# 640mk4.net
KiCad netlist of a schematic drawn in EAGLE
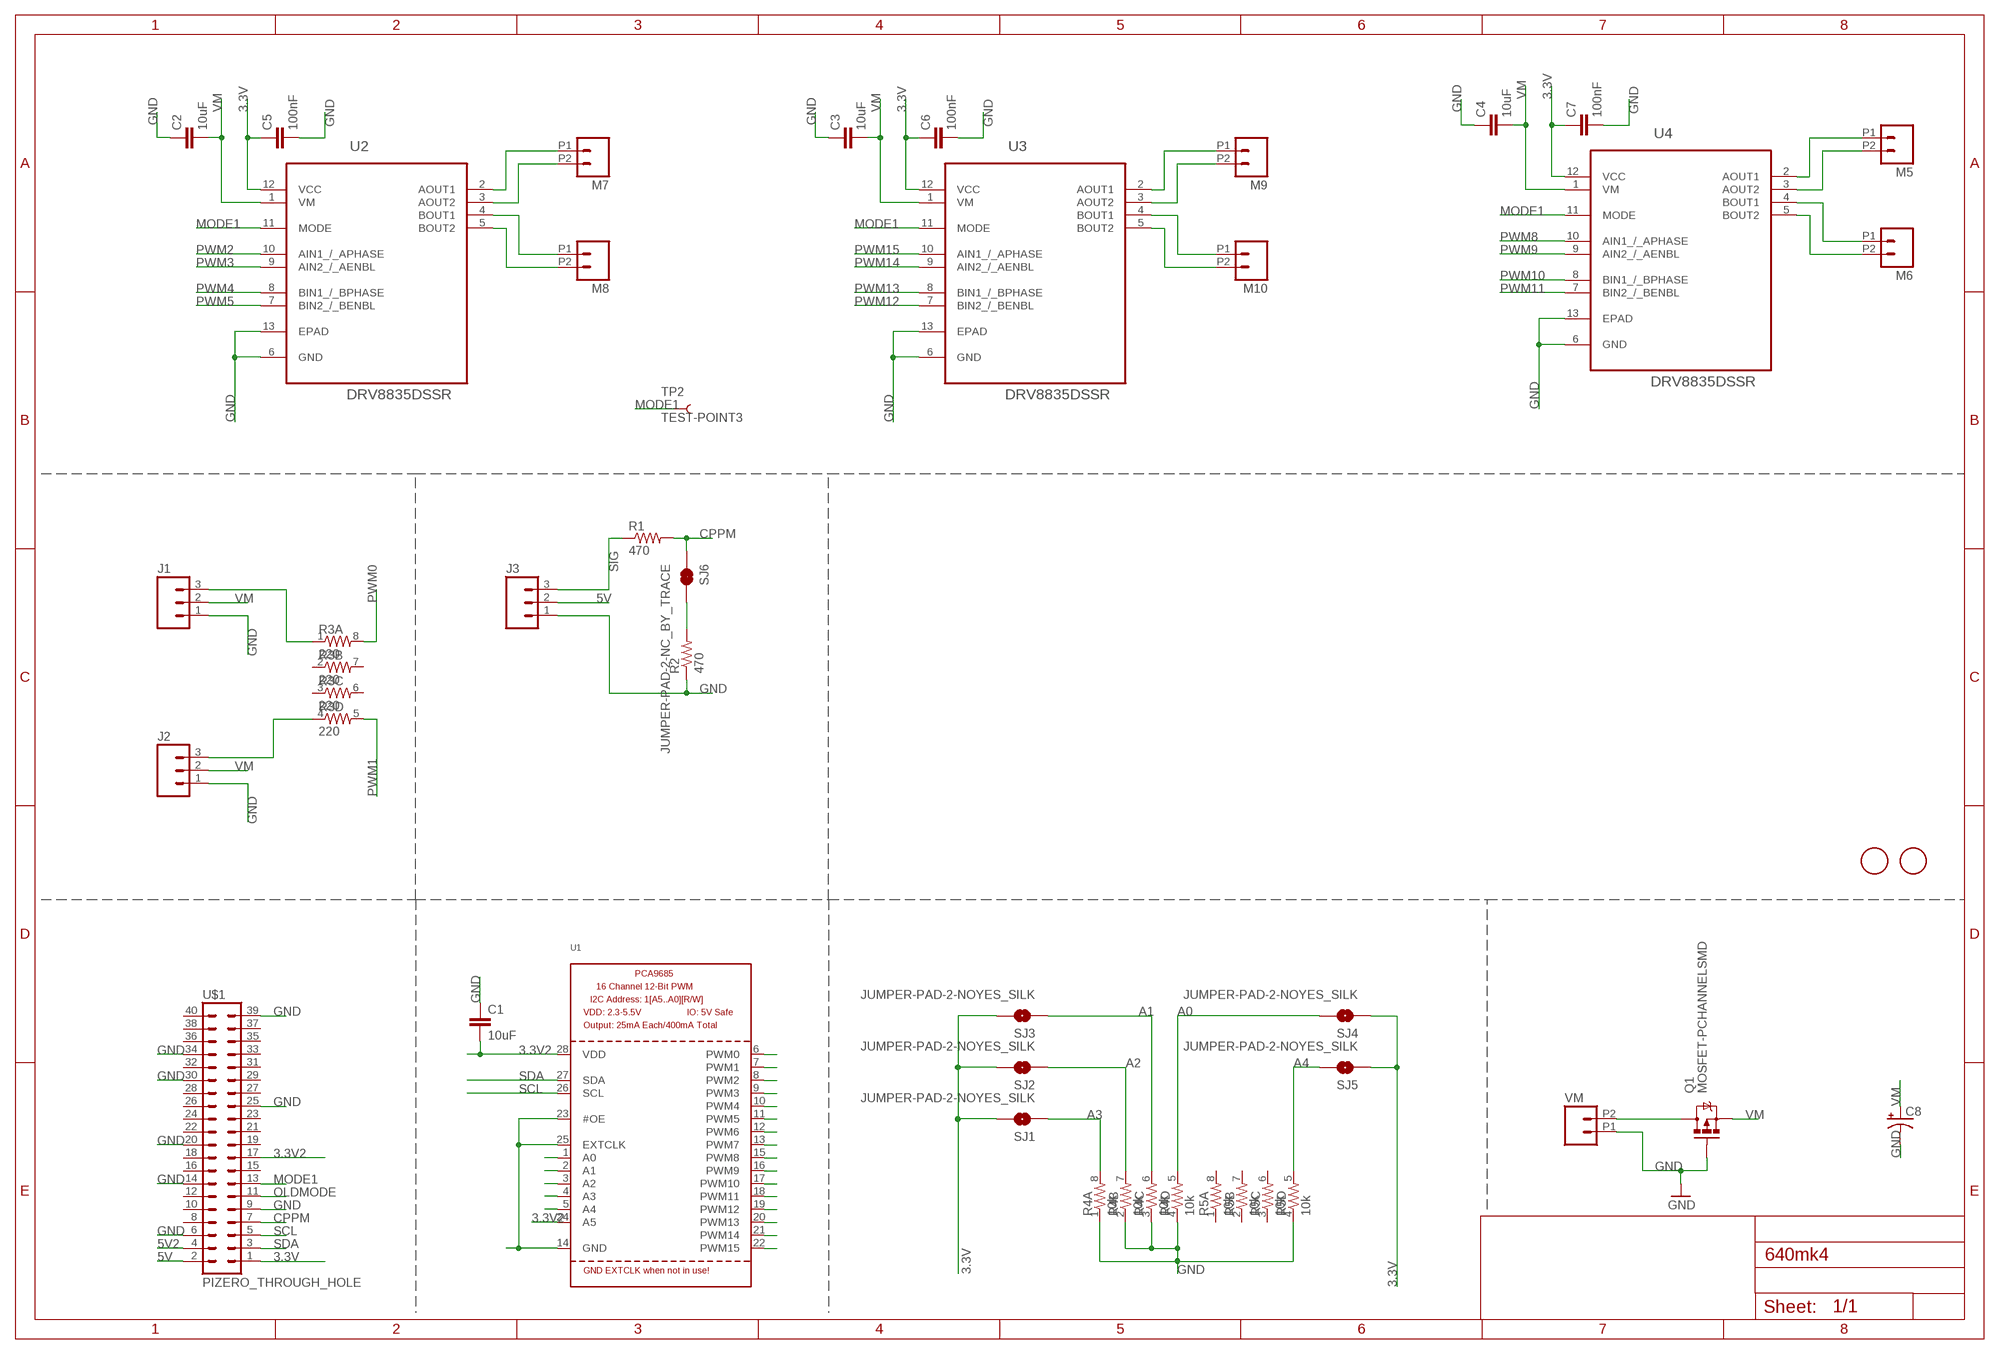
[diagram p0: schematic, sheet 1]

(export (version "E")
  (design (tool "Eeschema 10.0.6"))
  (components
    (comp (ref "C1")
      (value "10uF")
      (footprint "eagle-import:0805")
      (libsource (lib "eagle-import") (part "CAP0805"))
    )
    (comp (ref "C2")
      (value "10uF")
      (footprint "eagle-import:0805")
      (libsource (lib "eagle-import") (part "CAP0805"))
    )
    (comp (ref "C3")
      (value "10uF")
      (footprint "eagle-import:0805")
      (libsource (lib "eagle-import") (part "CAP0805"))
    )
    (comp (ref "C4")
      (value "10uF")
      (footprint "eagle-import:0805")
      (libsource (lib "eagle-import") (part "CAP0805"))
    )
    (comp (ref "C5")
      (value "100nF")
      (footprint "eagle-import:0805")
      (libsource (lib "eagle-import") (part "CAP0805"))
    )
    (comp (ref "C6")
      (value "100nF")
      (footprint "eagle-import:0805")
      (libsource (lib "eagle-import") (part "CAP0805"))
    )
    (comp (ref "C7")
      (value "100nF")
      (footprint "eagle-import:0805")
      (libsource (lib "eagle-import") (part "CAP0805"))
    )
    (comp (ref "C8")
      (value "CAP_POLPTH1")
      (footprint "eagle-import:CPOL-RADIAL-100UF-25V")
      (libsource (lib "eagle-import") (part "CAP_POLPTH1"))
    )
    (comp (ref "FID1")
      (value "FIDUCIAL")
      (footprint "eagle-import:FIDUCIAL_1MM")
      (libsource (lib "eagle-import") (part "FIDUCIAL"))
    )
    (comp (ref "FID2")
      (value "FIDUCIAL")
      (footprint "eagle-import:FIDUCIAL_1MM")
      (libsource (lib "eagle-import") (part "FIDUCIAL"))
    )
    (comp (ref "J1")
      (value "M03LOCK")
      (footprint "eagle-import:1X03_LOCK")
      (libsource (lib "eagle-import") (part "M03LOCK"))
    )
    (comp (ref "J2")
      (value "M03LOCK")
      (footprint "eagle-import:1X03_LOCK")
      (libsource (lib "eagle-import") (part "M03LOCK"))
    )
    (comp (ref "J3")
      (value "M03LOCK")
      (footprint "eagle-import:1X03_LOCK")
      (libsource (lib "eagle-import") (part "M03LOCK"))
    )
    (comp (ref "M5")
      (value "M022.54MM_SCREWTERM")
      (footprint "eagle-import:1X02_2.54_SCREWTERM")
      (libsource (lib "eagle-import") (part "M022.54MM_SCREWTERM"))
    )
    (comp (ref "M6")
      (value "M022.54MM_SCREWTERM")
      (footprint "eagle-import:1X02_2.54_SCREWTERM")
      (libsource (lib "eagle-import") (part "M022.54MM_SCREWTERM"))
    )
    (comp (ref "M7")
      (value "M022.54MM_SCREWTERM")
      (footprint "eagle-import:1X02_2.54_SCREWTERM")
      (libsource (lib "eagle-import") (part "M022.54MM_SCREWTERM"))
    )
    (comp (ref "M8")
      (value "M022.54MM_SCREWTERM")
      (footprint "eagle-import:1X02_2.54_SCREWTERM")
      (libsource (lib "eagle-import") (part "M022.54MM_SCREWTERM"))
    )
    (comp (ref "M9")
      (value "M022.54MM_SCREWTERM")
      (footprint "eagle-import:1X02_2.54_SCREWTERM")
      (libsource (lib "eagle-import") (part "M022.54MM_SCREWTERM"))
    )
    (comp (ref "M10")
      (value "M022.54MM_SCREWTERM")
      (footprint "eagle-import:1X02_2.54_SCREWTERM")
      (libsource (lib "eagle-import") (part "M022.54MM_SCREWTERM"))
    )
    (comp (ref "Q1")
      (value "MOSFET-PCHANNELSMD")
      (footprint "eagle-import:SOT23-3")
      (libsource (lib "eagle-import") (part "MOSFET-PCHANNELSMD"))
    )
    (comp (ref "R1")
      (value "470")
      (footprint "eagle-import:0805")
      (libsource (lib "eagle-import") (part "RESISTOR0805-RES"))
    )
    (comp (ref "R2")
      (value "470")
      (footprint "eagle-import:0805")
      (libsource (lib "eagle-import") (part "RESISTOR0805-RES"))
    )
    (comp (ref "R3")
      (value "220")
      (footprint "eagle-import:0603-ARV")
      (libsource (lib "eagle-import") (part "RESISTOR-ARRAY0603-ARV"))
    )
    (comp (ref "R4")
      (value "10k")
      (footprint "eagle-import:0603-ARV")
      (libsource (lib "eagle-import") (part "RESISTOR-ARRAY0603-ARV"))
    )
    (comp (ref "R5")
      (value "10k")
      (footprint "eagle-import:0603-ARV")
      (libsource (lib "eagle-import") (part "RESISTOR-ARRAY0603-ARV"))
    )
    (comp (ref "SJ1")
      (value "JUMPER-PAD-2-NOYES_SILK")
      (footprint "eagle-import:PAD-JUMPER-2-NO_YES_SILK")
      (libsource (lib "eagle-import") (part "JUMPER-PAD-2-NOYES_SILK"))
    )
    (comp (ref "SJ2")
      (value "JUMPER-PAD-2-NOYES_SILK")
      (footprint "eagle-import:PAD-JUMPER-2-NO_YES_SILK")
      (libsource (lib "eagle-import") (part "JUMPER-PAD-2-NOYES_SILK"))
    )
    (comp (ref "SJ3")
      (value "JUMPER-PAD-2-NOYES_SILK")
      (footprint "eagle-import:PAD-JUMPER-2-NO_YES_SILK")
      (libsource (lib "eagle-import") (part "JUMPER-PAD-2-NOYES_SILK"))
    )
    (comp (ref "SJ4")
      (value "JUMPER-PAD-2-NOYES_SILK")
      (footprint "eagle-import:PAD-JUMPER-2-NO_YES_SILK")
      (libsource (lib "eagle-import") (part "JUMPER-PAD-2-NOYES_SILK"))
    )
    (comp (ref "SJ5")
      (value "JUMPER-PAD-2-NOYES_SILK")
      (footprint "eagle-import:PAD-JUMPER-2-NO_YES_SILK")
      (libsource (lib "eagle-import") (part "JUMPER-PAD-2-NOYES_SILK"))
    )
    (comp (ref "SJ6")
      (value "JUMPER-PAD-2-NC_BY_TRACE")
      (footprint "eagle-import:PAD-JUMPER-2-NC_BY_TRACE_YES_SILK")
      (libsource (lib "eagle-import") (part "JUMPER-PAD-2-NC_BY_TRACE"))
    )
    (comp (ref "TP2")
      (value "TEST-POINT3")
      (footprint "eagle-import:PAD.03X.03")
      (libsource (lib "eagle-import") (part "TEST-POINT3"))
    )
    (comp (ref "U$1")
      (value "PIZERO_THROUGH_HOLE")
      (footprint "eagle-import:PIZERO_THOUGH_HOLE")
      (libsource (lib "eagle-import") (part "PIZERO_THROUGH_HOLE"))
    )
    (comp (ref "U1")
      (value "PCA9685")
      (footprint "eagle-import:TSSOP28")
      (libsource (lib "eagle-import") (part "PCA9685"))
    )
    (comp (ref "U2")
      (value "DRV8835DSSR")
      (footprint "eagle-import:SON50P200X300X80-13N")
      (fields (field (name "MPN") "DRV8835DSSR "))
      (libsource (lib "eagle-import") (part "DRV8835DSSR"))
    )
    (comp (ref "U3")
      (value "DRV8835DSSR")
      (footprint "eagle-import:SON50P200X300X80-13N")
      (fields (field (name "MPN") "DRV8835DSSR "))
      (libsource (lib "eagle-import") (part "DRV8835DSSR"))
    )
    (comp (ref "U4")
      (value "DRV8835DSSR")
      (footprint "eagle-import:SON50P200X300X80-13N")
      (fields (field (name "MPN") "DRV8835DSSR "))
      (libsource (lib "eagle-import") (part "DRV8835DSSR"))
    )
    (comp (ref "VM")
      (value "M022.54MM_SCREWTERM")
      (footprint "eagle-import:1X02_2.54_SCREWTERM")
      (libsource (lib "eagle-import") (part "M022.54MM_SCREWTERM"))
    )
  )
  (nets
    (net (code "1") (name "/3.3V") (class "Default")
      (node (ref "C5") (pin "1") (pinfunction "1_1") (pintype "passive"))
      (node (ref "C6") (pin "1") (pinfunction "1_1") (pintype "passive"))
      (node (ref "C7") (pin "1") (pinfunction "1_1") (pintype "passive"))
      (node (ref "SJ1") (pin "2") (pinfunction "2_2") (pintype "passive"))
      (node (ref "SJ2") (pin "2") (pinfunction "2_2") (pintype "passive"))
      (node (ref "SJ3") (pin "2") (pinfunction "2_2") (pintype "passive"))
      (node (ref "SJ4") (pin "1") (pinfunction "1_1") (pintype "passive"))
      (node (ref "SJ5") (pin "1") (pinfunction "1_1") (pintype "passive"))
      (node (ref "U$1") (pin "1") (pinfunction "1_1") (pintype "passive"))
      (node (ref "U2") (pin "12") (pinfunction "VCC_12") (pintype "power_in"))
      (node (ref "U3") (pin "12") (pinfunction "VCC_12") (pintype "power_in"))
      (node (ref "U4") (pin "12") (pinfunction "VCC_12") (pintype "power_in"))
    )
    (net (code "2") (name "/3.3V2") (class "Default")
      (node (ref "C1") (pin "2") (pinfunction "2_2") (pintype "passive"))
      (node (ref "U$1") (pin "17") (pinfunction "17_17") (pintype "passive"))
      (node (ref "U1") (pin "24") (pinfunction "A5_24") (pintype "bidirectional"))
      (node (ref "U1") (pin "28") (pinfunction "VDD_28") (pintype "power_in"))
    )
    (net (code "3") (name "/5V") (class "Default")
      (node (ref "J3") (pin "2") (pinfunction "2_2") (pintype "passive"))
      (node (ref "U$1") (pin "2") (pinfunction "2_2") (pintype "passive"))
    )
    (net (code "4") (name "/5V2") (class "Default")
      (node (ref "U$1") (pin "4") (pinfunction "4_4") (pintype "passive"))
    )
    (net (code "5") (name "/A0") (class "Default")
      (node (ref "R4") (pin "5") (pinfunction "2_5") (pintype "passive"))
      (node (ref "SJ4") (pin "2") (pinfunction "2_2") (pintype "passive"))
      (node (ref "U1") (pin "1") (pinfunction "A0_1") (pintype "bidirectional"))
    )
    (net (code "6") (name "/A1") (class "Default")
      (node (ref "R4") (pin "6") (pinfunction "2_6") (pintype "passive"))
      (node (ref "SJ3") (pin "1") (pinfunction "1_1") (pintype "passive"))
      (node (ref "U1") (pin "2") (pinfunction "A1_2") (pintype "bidirectional"))
    )
    (net (code "7") (name "/A2") (class "Default")
      (node (ref "R4") (pin "7") (pinfunction "2_7") (pintype "passive"))
      (node (ref "SJ2") (pin "1") (pinfunction "1_1") (pintype "passive"))
      (node (ref "U1") (pin "3") (pinfunction "A2_3") (pintype "bidirectional"))
    )
    (net (code "8") (name "/A3") (class "Default")
      (node (ref "R4") (pin "8") (pinfunction "2_8") (pintype "passive"))
      (node (ref "SJ1") (pin "1") (pinfunction "1_1") (pintype "passive"))
      (node (ref "U1") (pin "4") (pinfunction "A3_4") (pintype "bidirectional"))
    )
    (net (code "9") (name "/A4") (class "Default")
      (node (ref "R5") (pin "5") (pinfunction "2_5") (pintype "passive"))
      (node (ref "SJ5") (pin "2") (pinfunction "2_2") (pintype "passive"))
      (node (ref "U1") (pin "5") (pinfunction "A4_5") (pintype "bidirectional"))
    )
    (net (code "10") (name "/CPPM") (class "Default")
      (node (ref "R1") (pin "2") (pinfunction "2_2") (pintype "passive"))
      (node (ref "SJ6") (pin "1") (pinfunction "1_1") (pintype "passive"))
      (node (ref "U$1") (pin "7") (pinfunction "7_7") (pintype "passive"))
    )
    (net (code "11") (name "/MODE1") (class "Default")
      (node (ref "TP2") (pin "P$1") (pinfunction "1_P$1") (pintype "bidirectional"))
      (node (ref "U$1") (pin "13") (pinfunction "13_13") (pintype "passive"))
      (node (ref "U2") (pin "11") (pinfunction "MODE_11") (pintype "input"))
      (node (ref "U3") (pin "11") (pinfunction "MODE_11") (pintype "input"))
      (node (ref "U4") (pin "11") (pinfunction "MODE_11") (pintype "input"))
    )
    (net (code "12") (name "/OLDMODE") (class "Default")
      (node (ref "U$1") (pin "11") (pinfunction "11_11") (pintype "passive"))
    )
    (net (code "13") (name "/PWM0") (class "Default")
      (node (ref "R3") (pin "8") (pinfunction "2_8") (pintype "passive"))
      (node (ref "U1") (pin "6") (pinfunction "PWM0_6") (pintype "output"))
    )
    (net (code "14") (name "/PWM1") (class "Default")
      (node (ref "R3") (pin "5") (pinfunction "2_5") (pintype "passive"))
      (node (ref "U1") (pin "7") (pinfunction "PWM1_7") (pintype "output"))
    )
    (net (code "15") (name "/PWM2") (class "Default")
      (node (ref "U1") (pin "8") (pinfunction "PWM2_8") (pintype "output"))
      (node (ref "U2") (pin "10") (pinfunction "AIN1_/_APHASE_10") (pintype "input"))
    )
    (net (code "16") (name "/PWM3") (class "Default")
      (node (ref "U1") (pin "9") (pinfunction "PWM3_9") (pintype "output"))
      (node (ref "U2") (pin "9") (pinfunction "AIN2_/_AENBL_9") (pintype "input"))
    )
    (net (code "17") (name "/PWM4") (class "Default")
      (node (ref "U1") (pin "10") (pinfunction "PWM4_10") (pintype "output"))
      (node (ref "U2") (pin "8") (pinfunction "BIN1_/_BPHASE_8") (pintype "input"))
    )
    (net (code "18") (name "/PWM5") (class "Default")
      (node (ref "U1") (pin "11") (pinfunction "PWM5_11") (pintype "output"))
      (node (ref "U2") (pin "7") (pinfunction "BIN2_/_BENBL_7") (pintype "input"))
    )
    (net (code "19") (name "/PWM8") (class "Default")
      (node (ref "U1") (pin "15") (pinfunction "PWM8_15") (pintype "output"))
      (node (ref "U4") (pin "10") (pinfunction "AIN1_/_APHASE_10") (pintype "input"))
    )
    (net (code "20") (name "/PWM9") (class "Default")
      (node (ref "U1") (pin "16") (pinfunction "PWM9_16") (pintype "output"))
      (node (ref "U4") (pin "9") (pinfunction "AIN2_/_AENBL_9") (pintype "input"))
    )
    (net (code "21") (name "/PWM10") (class "Default")
      (node (ref "U1") (pin "17") (pinfunction "PWM10_17") (pintype "output"))
      (node (ref "U4") (pin "8") (pinfunction "BIN1_/_BPHASE_8") (pintype "input"))
    )
    (net (code "22") (name "/PWM11") (class "Default")
      (node (ref "U1") (pin "18") (pinfunction "PWM11_18") (pintype "output"))
      (node (ref "U4") (pin "7") (pinfunction "BIN2_/_BENBL_7") (pintype "input"))
    )
    (net (code "23") (name "/PWM12") (class "Default")
      (node (ref "U1") (pin "19") (pinfunction "PWM12_19") (pintype "output"))
      (node (ref "U3") (pin "7") (pinfunction "BIN2_/_BENBL_7") (pintype "input"))
    )
    (net (code "24") (name "/PWM13") (class "Default")
      (node (ref "U1") (pin "20") (pinfunction "PWM13_20") (pintype "output"))
      (node (ref "U3") (pin "8") (pinfunction "BIN1_/_BPHASE_8") (pintype "input"))
    )
    (net (code "25") (name "/PWM14") (class "Default")
      (node (ref "U1") (pin "21") (pinfunction "PWM14_21") (pintype "output"))
      (node (ref "U3") (pin "9") (pinfunction "AIN2_/_AENBL_9") (pintype "input"))
    )
    (net (code "26") (name "/PWM15") (class "Default")
      (node (ref "U1") (pin "22") (pinfunction "PWM15_22") (pintype "output"))
      (node (ref "U3") (pin "10") (pinfunction "AIN1_/_APHASE_10") (pintype "input"))
    )
    (net (code "27") (name "/SCL") (class "Default")
      (node (ref "U$1") (pin "5") (pinfunction "5_5") (pintype "passive"))
      (node (ref "U1") (pin "26") (pinfunction "SCL_26") (pintype "bidirectional"))
    )
    (net (code "28") (name "/SDA") (class "Default")
      (node (ref "U$1") (pin "3") (pinfunction "3_3") (pintype "passive"))
      (node (ref "U1") (pin "27") (pinfunction "SDA_27") (pintype "bidirectional"))
    )
    (net (code "29") (name "/SIG") (class "Default")
      (node (ref "J3") (pin "3") (pinfunction "3_3") (pintype "passive"))
      (node (ref "R1") (pin "1") (pinfunction "1_1") (pintype "passive"))
    )
    (net (code "30") (name "/VM") (class "Default")
      (node (ref "C2") (pin "2") (pinfunction "2_2") (pintype "passive"))
      (node (ref "C3") (pin "2") (pinfunction "2_2") (pintype "passive"))
      (node (ref "C4") (pin "2") (pinfunction "2_2") (pintype "passive"))
      (node (ref "C8") (pin "1") (pinfunction "+_1") (pintype "passive"))
      (node (ref "J1") (pin "2") (pinfunction "2_2") (pintype "passive"))
      (node (ref "J2") (pin "2") (pinfunction "2_2") (pintype "passive"))
      (node (ref "Q1") (pin "2") (pinfunction "S_2") (pintype "passive"))
      (node (ref "U2") (pin "1") (pinfunction "VM_1") (pintype "power_in"))
      (node (ref "U3") (pin "1") (pinfunction "VM_1") (pintype "power_in"))
      (node (ref "U4") (pin "1") (pinfunction "VM_1") (pintype "power_in"))
    )
    (net (code "31") (name "GND") (class "Default")
      (node (ref "C1") (pin "1") (pinfunction "1_1") (pintype "passive"))
      (node (ref "C2") (pin "1") (pinfunction "1_1") (pintype "passive"))
      (node (ref "C3") (pin "1") (pinfunction "1_1") (pintype "passive"))
      (node (ref "C4") (pin "1") (pinfunction "1_1") (pintype "passive"))
      (node (ref "C5") (pin "2") (pinfunction "2_2") (pintype "passive"))
      (node (ref "C6") (pin "2") (pinfunction "2_2") (pintype "passive"))
      (node (ref "C7") (pin "2") (pinfunction "2_2") (pintype "passive"))
      (node (ref "C8") (pin "2") (pinfunction "-_2") (pintype "passive"))
      (node (ref "J1") (pin "1") (pinfunction "1_1") (pintype "passive"))
      (node (ref "J2") (pin "1") (pinfunction "1_1") (pintype "passive"))
      (node (ref "J3") (pin "1") (pinfunction "1_1") (pintype "passive"))
      (node (ref "Q1") (pin "1") (pinfunction "G_1") (pintype "passive"))
      (node (ref "R2") (pin "1") (pinfunction "1_1") (pintype "passive"))
      (node (ref "R4") (pin "1") (pinfunction "1_1") (pintype "passive"))
      (node (ref "R4") (pin "2") (pinfunction "1_2") (pintype "passive"))
      (node (ref "R4") (pin "3") (pinfunction "1_3") (pintype "passive"))
      (node (ref "R4") (pin "4") (pinfunction "1_4") (pintype "passive"))
      (node (ref "R5") (pin "4") (pinfunction "1_4") (pintype "passive"))
      (node (ref "U$1") (pin "14") (pinfunction "14_14") (pintype "passive"))
      (node (ref "U$1") (pin "20") (pinfunction "20_20") (pintype "passive"))
      (node (ref "U$1") (pin "25") (pinfunction "25_25") (pintype "passive"))
      (node (ref "U$1") (pin "30") (pinfunction "30_30") (pintype "passive"))
      (node (ref "U$1") (pin "34") (pinfunction "34_34") (pintype "passive"))
      (node (ref "U$1") (pin "39") (pinfunction "39_39") (pintype "passive"))
      (node (ref "U$1") (pin "6") (pinfunction "6_6") (pintype "passive"))
      (node (ref "U$1") (pin "9") (pinfunction "9_9") (pintype "passive"))
      (node (ref "U1") (pin "14") (pinfunction "GND_14") (pintype "power_in"))
      (node (ref "U1") (pin "23") (pinfunction "#OE_23") (pintype "input"))
      (node (ref "U1") (pin "25") (pinfunction "EXTCLK_25") (pintype "input"))
      (node (ref "U2") (pin "13") (pinfunction "EPAD_13") (pintype "passive"))
      (node (ref "U2") (pin "6") (pinfunction "GND_6") (pintype "passive"))
      (node (ref "U3") (pin "13") (pinfunction "EPAD_13") (pintype "passive"))
      (node (ref "U3") (pin "6") (pinfunction "GND_6") (pintype "passive"))
      (node (ref "U4") (pin "13") (pinfunction "EPAD_13") (pintype "passive"))
      (node (ref "U4") (pin "6") (pinfunction "GND_6") (pintype "passive"))
      (node (ref "VM") (pin "P1") (pinfunction "1_P1") (pintype "passive"))
    )
    (net (code "32") (name "Net-(J1-Pad3)") (class "Default")
      (node (ref "J1") (pin "3") (pinfunction "3_3") (pintype "passive"))
      (node (ref "R3") (pin "1") (pinfunction "1_1") (pintype "passive"))
    )
    (net (code "33") (name "Net-(M5-1)") (class "Default")
      (node (ref "M5") (pin "P1") (pinfunction "1_P1") (pintype "passive"))
      (node (ref "U4") (pin "2") (pinfunction "AOUT1_2") (pintype "output"))
    )
    (net (code "34") (name "Net-(M5-2)") (class "Default")
      (node (ref "M5") (pin "P2") (pinfunction "2_P2") (pintype "passive"))
      (node (ref "U4") (pin "3") (pinfunction "AOUT2_3") (pintype "output"))
    )
    (net (code "35") (name "Net-(M6-1)") (class "Default")
      (node (ref "M6") (pin "P1") (pinfunction "1_P1") (pintype "passive"))
      (node (ref "U4") (pin "4") (pinfunction "BOUT1_4") (pintype "output"))
    )
    (net (code "36") (name "Net-(M6-2)") (class "Default")
      (node (ref "M6") (pin "P2") (pinfunction "2_P2") (pintype "passive"))
      (node (ref "U4") (pin "5") (pinfunction "BOUT2_5") (pintype "output"))
    )
    (net (code "37") (name "Net-(M7-1)") (class "Default")
      (node (ref "M7") (pin "P1") (pinfunction "1_P1") (pintype "passive"))
      (node (ref "U2") (pin "2") (pinfunction "AOUT1_2") (pintype "output"))
    )
    (net (code "38") (name "Net-(M7-2)") (class "Default")
      (node (ref "M7") (pin "P2") (pinfunction "2_P2") (pintype "passive"))
      (node (ref "U2") (pin "3") (pinfunction "AOUT2_3") (pintype "output"))
    )
    (net (code "39") (name "Net-(M8-1)") (class "Default")
      (node (ref "M8") (pin "P1") (pinfunction "1_P1") (pintype "passive"))
      (node (ref "U2") (pin "4") (pinfunction "BOUT1_4") (pintype "output"))
    )
    (net (code "40") (name "Net-(M8-2)") (class "Default")
      (node (ref "M8") (pin "P2") (pinfunction "2_P2") (pintype "passive"))
      (node (ref "U2") (pin "5") (pinfunction "BOUT2_5") (pintype "output"))
    )
    (net (code "41") (name "Net-(M9-1)") (class "Default")
      (node (ref "M9") (pin "P1") (pinfunction "1_P1") (pintype "passive"))
      (node (ref "U3") (pin "2") (pinfunction "AOUT1_2") (pintype "output"))
    )
    (net (code "42") (name "Net-(M9-2)") (class "Default")
      (node (ref "M9") (pin "P2") (pinfunction "2_P2") (pintype "passive"))
      (node (ref "U3") (pin "3") (pinfunction "AOUT2_3") (pintype "output"))
    )
    (net (code "43") (name "Net-(M10-1)") (class "Default")
      (node (ref "M10") (pin "P1") (pinfunction "1_P1") (pintype "passive"))
      (node (ref "U3") (pin "4") (pinfunction "BOUT1_4") (pintype "output"))
    )
    (net (code "44") (name "Net-(M10-2)") (class "Default")
      (node (ref "M10") (pin "P2") (pinfunction "2_P2") (pintype "passive"))
      (node (ref "U3") (pin "5") (pinfunction "BOUT2_5") (pintype "output"))
    )
    (net (code "45") (name "Net-(Q1-D)") (class "Default")
      (node (ref "Q1") (pin "3") (pinfunction "D_3") (pintype "passive"))
      (node (ref "VM") (pin "P2") (pinfunction "2_P2") (pintype "passive"))
    )
    (net (code "46") (name "Net-(R2-Pad2)") (class "Default")
      (node (ref "R2") (pin "2") (pinfunction "2_2") (pintype "passive"))
      (node (ref "SJ6") (pin "2") (pinfunction "2_2") (pintype "passive"))
    )
    (net (code "47") (name "Net-(R3D-1)") (class "Default")
      (node (ref "J2") (pin "3") (pinfunction "3_3") (pintype "passive"))
      (node (ref "R3") (pin "4") (pinfunction "1_4") (pintype "passive"))
    )
    (net (code "48") (name "unconnected-(R3B-1-Pad2)") (class "Default")
      (node (ref "R3") (pin "2") (pinfunction "1_2") (pintype "passive"))
    )
    (net (code "49") (name "unconnected-(R3B-2-Pad7)") (class "Default")
      (node (ref "R3") (pin "7") (pinfunction "2_7") (pintype "passive"))
    )
    (net (code "50") (name "unconnected-(R3C-1-Pad3)") (class "Default")
      (node (ref "R3") (pin "3") (pinfunction "1_3") (pintype "passive"))
    )
    (net (code "51") (name "unconnected-(R3C-2-Pad6)") (class "Default")
      (node (ref "R3") (pin "6") (pinfunction "2_6") (pintype "passive"))
    )
    (net (code "52") (name "unconnected-(R5-Pad1)") (class "Default")
      (node (ref "R5") (pin "1") (pinfunction "1_1") (pintype "passive"))
    )
    (net (code "53") (name "unconnected-(R5A-2-Pad8)") (class "Default")
      (node (ref "R5") (pin "8") (pinfunction "2_8") (pintype "passive"))
    )
    (net (code "54") (name "unconnected-(R5B-1-Pad2)") (class "Default")
      (node (ref "R5") (pin "2") (pinfunction "1_2") (pintype "passive"))
    )
    (net (code "55") (name "unconnected-(R5B-2-Pad7)") (class "Default")
      (node (ref "R5") (pin "7") (pinfunction "2_7") (pintype "passive"))
    )
    (net (code "56") (name "unconnected-(R5C-1-Pad3)") (class "Default")
      (node (ref "R5") (pin "3") (pinfunction "1_3") (pintype "passive"))
    )
    (net (code "57") (name "unconnected-(R5C-2-Pad6)") (class "Default")
      (node (ref "R5") (pin "6") (pinfunction "2_6") (pintype "passive"))
    )
    (net (code "58") (name "unconnected-(U$1-Pad8)") (class "Default")
      (node (ref "U$1") (pin "8") (pinfunction "8_8") (pintype "passive"))
    )
    (net (code "59") (name "unconnected-(U$1-Pad10)") (class "Default")
      (node (ref "U$1") (pin "10") (pinfunction "10_10") (pintype "passive"))
    )
    (net (code "60") (name "unconnected-(U$1-Pad12)") (class "Default")
      (node (ref "U$1") (pin "12") (pinfunction "12_12") (pintype "passive"))
    )
    (net (code "61") (name "unconnected-(U$1-Pad15)") (class "Default")
      (node (ref "U$1") (pin "15") (pinfunction "15_15") (pintype "passive"))
    )
    (net (code "62") (name "unconnected-(U$1-Pad16)") (class "Default")
      (node (ref "U$1") (pin "16") (pinfunction "16_16") (pintype "passive"))
    )
    (net (code "63") (name "unconnected-(U$1-Pad18)") (class "Default")
      (node (ref "U$1") (pin "18") (pinfunction "18_18") (pintype "passive"))
    )
    (net (code "64") (name "unconnected-(U$1-Pad19)") (class "Default")
      (node (ref "U$1") (pin "19") (pinfunction "19_19") (pintype "passive"))
    )
    (net (code "65") (name "unconnected-(U$1-Pad21)") (class "Default")
      (node (ref "U$1") (pin "21") (pinfunction "21_21") (pintype "passive"))
    )
    (net (code "66") (name "unconnected-(U$1-Pad22)") (class "Default")
      (node (ref "U$1") (pin "22") (pinfunction "22_22") (pintype "passive"))
    )
    (net (code "67") (name "unconnected-(U$1-Pad23)") (class "Default")
      (node (ref "U$1") (pin "23") (pinfunction "23_23") (pintype "passive"))
    )
    (net (code "68") (name "unconnected-(U$1-Pad24)") (class "Default")
      (node (ref "U$1") (pin "24") (pinfunction "24_24") (pintype "passive"))
    )
    (net (code "69") (name "unconnected-(U$1-Pad26)") (class "Default")
      (node (ref "U$1") (pin "26") (pinfunction "26_26") (pintype "passive"))
    )
    (net (code "70") (name "unconnected-(U$1-Pad27)") (class "Default")
      (node (ref "U$1") (pin "27") (pinfunction "27_27") (pintype "passive"))
    )
    (net (code "71") (name "unconnected-(U$1-Pad28)") (class "Default")
      (node (ref "U$1") (pin "28") (pinfunction "28_28") (pintype "passive"))
    )
    (net (code "72") (name "unconnected-(U$1-Pad29)") (class "Default")
      (node (ref "U$1") (pin "29") (pinfunction "29_29") (pintype "passive"))
    )
    (net (code "73") (name "unconnected-(U$1-Pad31)") (class "Default")
      (node (ref "U$1") (pin "31") (pinfunction "31_31") (pintype "passive"))
    )
    (net (code "74") (name "unconnected-(U$1-Pad32)") (class "Default")
      (node (ref "U$1") (pin "32") (pinfunction "32_32") (pintype "passive"))
    )
    (net (code "75") (name "unconnected-(U$1-Pad33)") (class "Default")
      (node (ref "U$1") (pin "33") (pinfunction "33_33") (pintype "passive"))
    )
    (net (code "76") (name "unconnected-(U$1-Pad35)") (class "Default")
      (node (ref "U$1") (pin "35") (pinfunction "35_35") (pintype "passive"))
    )
    (net (code "77") (name "unconnected-(U$1-Pad36)") (class "Default")
      (node (ref "U$1") (pin "36") (pinfunction "36_36") (pintype "passive"))
    )
    (net (code "78") (name "unconnected-(U$1-Pad37)") (class "Default")
      (node (ref "U$1") (pin "37") (pinfunction "37_37") (pintype "passive"))
    )
    (net (code "79") (name "unconnected-(U$1-Pad38)") (class "Default")
      (node (ref "U$1") (pin "38") (pinfunction "38_38") (pintype "passive"))
    )
    (net (code "80") (name "unconnected-(U$1-Pad40)") (class "Default")
      (node (ref "U$1") (pin "40") (pinfunction "40_40") (pintype "passive"))
    )
    (net (code "81") (name "unconnected-(U1-PWM6-Pad12)") (class "Default")
      (node (ref "U1") (pin "12") (pinfunction "PWM6_12") (pintype "output"))
    )
    (net (code "82") (name "unconnected-(U1-PWM7-Pad13)") (class "Default")
      (node (ref "U1") (pin "13") (pinfunction "PWM7_13") (pintype "output"))
    )
  )
)
